# Sensor_Multiplexation.net
KiCad netlist of a schematic drawn in Altium Designer
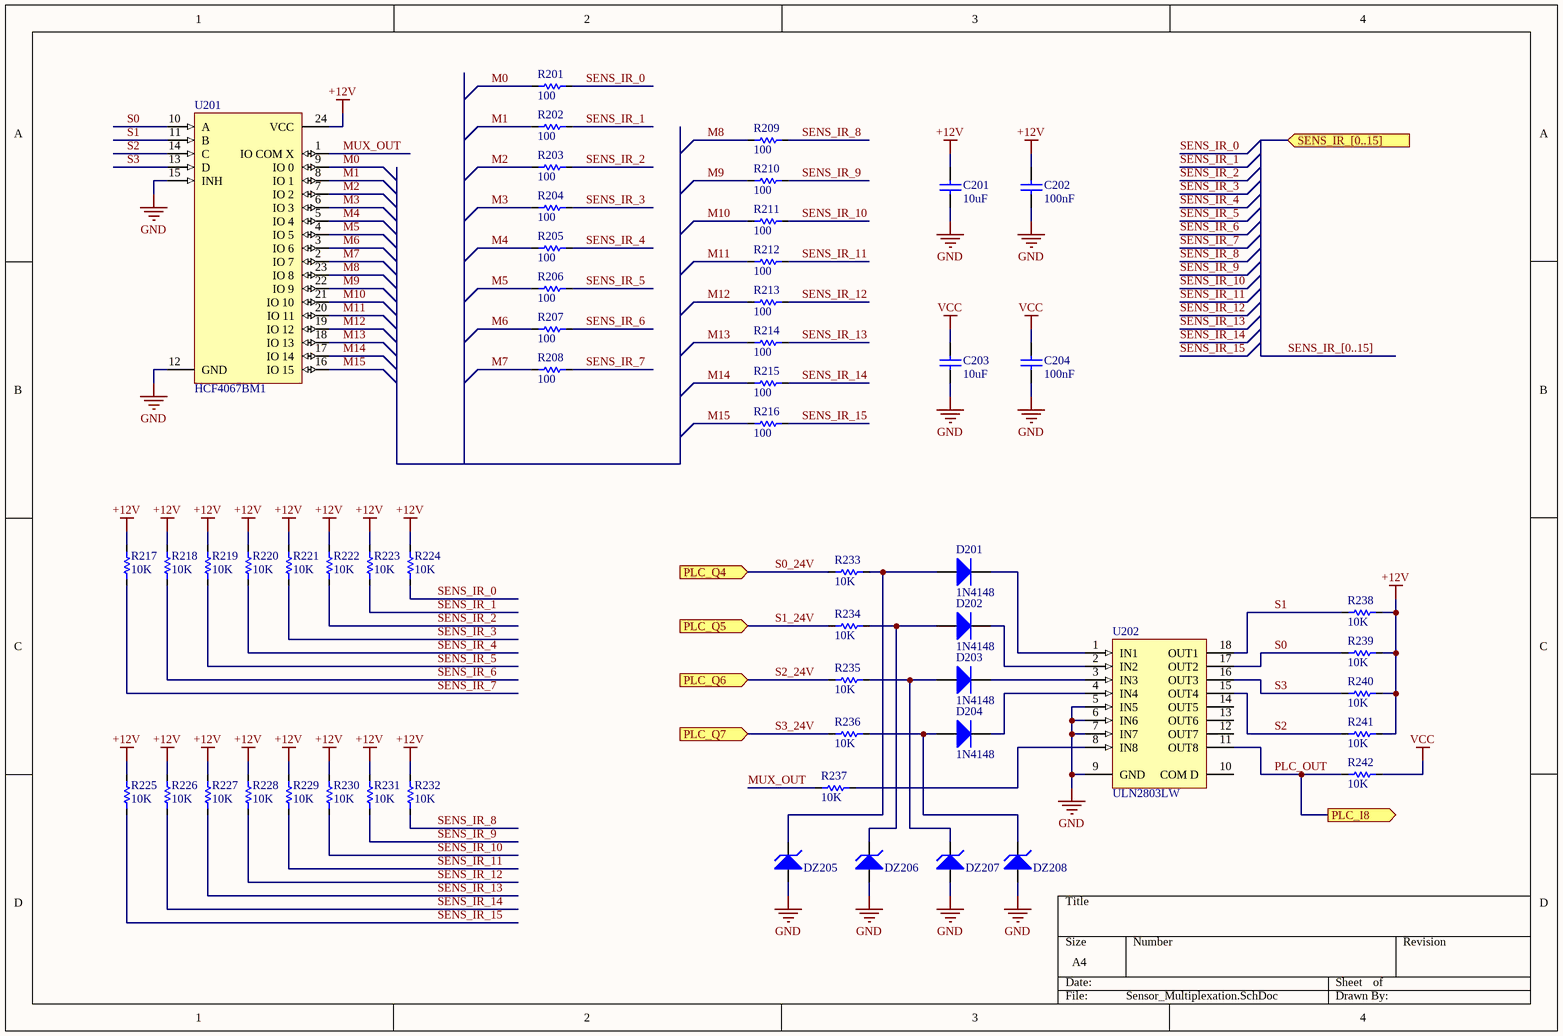
[diagram p0: Sensor_Multiplexation.SchDoc]

(export (version "E")
  (design (tool "Eeschema 10.0.6"))
  (components
    (comp (ref "C201")
      (value "Cap Ceramico SMD")
      (footprint "C0603")
      (description "Cap Ceramico SMD 0805")
      (fields (field (name "VALOR") "10uF"))
      (libsource (lib "RUF-Dispositivos-Grales") (part "Cap Ceramico SMD"))
    )
    (comp (ref "C202")
      (value "Cap Ceramico SMD")
      (footprint "C0603")
      (description "Cap Ceramico SMD 0805")
      (fields (field (name "VALOR") "100nF"))
      (libsource (lib "RUF-Dispositivos-Grales") (part "Cap Ceramico SMD"))
    )
    (comp (ref "C203")
      (value "Cap Ceramico SMD")
      (footprint "C0603")
      (description "Cap Ceramico SMD 0805")
      (fields (field (name "VALOR") "10uF"))
      (libsource (lib "RUF-Dispositivos-Grales") (part "Cap Ceramico SMD"))
    )
    (comp (ref "C204")
      (value "Cap Ceramico SMD")
      (footprint "C0603")
      (description "Cap Ceramico SMD 0805")
      (fields (field (name "VALOR") "100nF"))
      (libsource (lib "RUF-Dispositivos-Grales") (part "Cap Ceramico SMD"))
    )
    (comp (ref "D201")
      (value "Diodo Rectificador SMD")
      (footprint "SOD-80")
      (description "Diodo Rectificador")
      (fields (field (name "VALOR") "1N4148"))
      (libsource (lib "RUF-Dispositivos-Grales") (part "Diodo Rectificador SMD"))
    )
    (comp (ref "D202")
      (value "Diodo Rectificador SMD")
      (footprint "SOD-80")
      (description "Diodo Rectificador")
      (fields (field (name "VALOR") "1N4148"))
      (libsource (lib "RUF-Dispositivos-Grales") (part "Diodo Rectificador SMD"))
    )
    (comp (ref "D203")
      (value "Diodo Rectificador SMD")
      (footprint "SOD-80")
      (description "Diodo Rectificador")
      (fields (field (name "VALOR") "1N4148"))
      (libsource (lib "RUF-Dispositivos-Grales") (part "Diodo Rectificador SMD"))
    )
    (comp (ref "D204")
      (value "Diodo Rectificador SMD")
      (footprint "SOD-80")
      (description "Diodo Rectificador")
      (fields (field (name "VALOR") "1N4148"))
      (libsource (lib "RUF-Dispositivos-Grales") (part "Diodo Rectificador SMD"))
    )
    (comp (ref "DZ205")
      (value "Diodo Zenner SMD")
      (footprint "SOD-80")
      (description "Diodo zenner SMD")
      (libsource (lib "RUF-Dispositivos-Grales") (part "Diodo Zenner SMD"))
    )
    (comp (ref "DZ206")
      (value "Diodo Zenner SMD")
      (footprint "SOD-80")
      (description "Diodo zenner SMD")
      (libsource (lib "RUF-Dispositivos-Grales") (part "Diodo Zenner SMD"))
    )
    (comp (ref "DZ207")
      (value "Diodo Zenner SMD")
      (footprint "SOD-80")
      (description "Diodo zenner SMD")
      (libsource (lib "RUF-Dispositivos-Grales") (part "Diodo Zenner SMD"))
    )
    (comp (ref "DZ208")
      (value "Diodo Zenner SMD")
      (footprint "SOD-80")
      (description "Diodo zenner SMD")
      (libsource (lib "RUF-Dispositivos-Grales") (part "Diodo Zenner SMD"))
    )
    (comp (ref "R201")
      (value "Res SMD")
      (footprint "R0603")
      (description "Res Smd")
      (fields (field (name "VALOR") "100"))
      (libsource (lib "RUF-Dispositivos-Grales") (part "Res SMD"))
    )
    (comp (ref "R202")
      (value "Res SMD")
      (footprint "R0603")
      (description "Res Smd")
      (fields (field (name "VALOR") "100"))
      (libsource (lib "RUF-Dispositivos-Grales") (part "Res SMD"))
    )
    (comp (ref "R203")
      (value "Res SMD")
      (footprint "R0603")
      (description "Res Smd")
      (fields (field (name "VALOR") "100"))
      (libsource (lib "RUF-Dispositivos-Grales") (part "Res SMD"))
    )
    (comp (ref "R204")
      (value "Res SMD")
      (footprint "R0603")
      (description "Res Smd")
      (fields (field (name "VALOR") "100"))
      (libsource (lib "RUF-Dispositivos-Grales") (part "Res SMD"))
    )
    (comp (ref "R205")
      (value "Res SMD")
      (footprint "R0603")
      (description "Res Smd")
      (fields (field (name "VALOR") "100"))
      (libsource (lib "RUF-Dispositivos-Grales") (part "Res SMD"))
    )
    (comp (ref "R206")
      (value "Res SMD")
      (footprint "R0603")
      (description "Res Smd")
      (fields (field (name "VALOR") "100"))
      (libsource (lib "RUF-Dispositivos-Grales") (part "Res SMD"))
    )
    (comp (ref "R207")
      (value "Res SMD")
      (footprint "R0603")
      (description "Res Smd")
      (fields (field (name "VALOR") "100"))
      (libsource (lib "RUF-Dispositivos-Grales") (part "Res SMD"))
    )
    (comp (ref "R208")
      (value "Res SMD")
      (footprint "R0603")
      (description "Res Smd")
      (fields (field (name "VALOR") "100"))
      (libsource (lib "RUF-Dispositivos-Grales") (part "Res SMD"))
    )
    (comp (ref "R209")
      (value "Res SMD")
      (footprint "R0603")
      (description "Res Smd")
      (fields (field (name "VALOR") "100"))
      (libsource (lib "RUF-Dispositivos-Grales") (part "Res SMD"))
    )
    (comp (ref "R210")
      (value "Res SMD")
      (footprint "R0603")
      (description "Res Smd")
      (fields (field (name "VALOR") "100"))
      (libsource (lib "RUF-Dispositivos-Grales") (part "Res SMD"))
    )
    (comp (ref "R211")
      (value "Res SMD")
      (footprint "R0603")
      (description "Res Smd")
      (fields (field (name "VALOR") "100"))
      (libsource (lib "RUF-Dispositivos-Grales") (part "Res SMD"))
    )
    (comp (ref "R212")
      (value "Res SMD")
      (footprint "R0603")
      (description "Res Smd")
      (fields (field (name "VALOR") "100"))
      (libsource (lib "RUF-Dispositivos-Grales") (part "Res SMD"))
    )
    (comp (ref "R213")
      (value "Res SMD")
      (footprint "R0603")
      (description "Res Smd")
      (fields (field (name "VALOR") "100"))
      (libsource (lib "RUF-Dispositivos-Grales") (part "Res SMD"))
    )
    (comp (ref "R214")
      (value "Res SMD")
      (footprint "R0603")
      (description "Res Smd")
      (fields (field (name "VALOR") "100"))
      (libsource (lib "RUF-Dispositivos-Grales") (part "Res SMD"))
    )
    (comp (ref "R215")
      (value "Res SMD")
      (footprint "R0603")
      (description "Res Smd")
      (fields (field (name "VALOR") "100"))
      (libsource (lib "RUF-Dispositivos-Grales") (part "Res SMD"))
    )
    (comp (ref "R216")
      (value "Res SMD")
      (footprint "R0603")
      (description "Res Smd")
      (fields (field (name "VALOR") "100"))
      (libsource (lib "RUF-Dispositivos-Grales") (part "Res SMD"))
    )
    (comp (ref "R217")
      (value "Res SMD")
      (footprint "R0603")
      (description "Res Smd")
      (fields (field (name "VALOR") "10K"))
      (libsource (lib "RUF-Dispositivos-Grales") (part "Res SMD"))
    )
    (comp (ref "R218")
      (value "Res SMD")
      (footprint "R0603")
      (description "Res Smd")
      (fields (field (name "VALOR") "10K"))
      (libsource (lib "RUF-Dispositivos-Grales") (part "Res SMD"))
    )
    (comp (ref "R219")
      (value "Res SMD")
      (footprint "R0603")
      (description "Res Smd")
      (fields (field (name "VALOR") "10K"))
      (libsource (lib "RUF-Dispositivos-Grales") (part "Res SMD"))
    )
    (comp (ref "R220")
      (value "Res SMD")
      (footprint "R0603")
      (description "Res Smd")
      (fields (field (name "VALOR") "10K"))
      (libsource (lib "RUF-Dispositivos-Grales") (part "Res SMD"))
    )
    (comp (ref "R221")
      (value "Res SMD")
      (footprint "R0603")
      (description "Res Smd")
      (fields (field (name "VALOR") "10K"))
      (libsource (lib "RUF-Dispositivos-Grales") (part "Res SMD"))
    )
    (comp (ref "R222")
      (value "Res SMD")
      (footprint "R0603")
      (description "Res Smd")
      (fields (field (name "VALOR") "10K"))
      (libsource (lib "RUF-Dispositivos-Grales") (part "Res SMD"))
    )
    (comp (ref "R223")
      (value "Res SMD")
      (footprint "R0603")
      (description "Res Smd")
      (fields (field (name "VALOR") "10K"))
      (libsource (lib "RUF-Dispositivos-Grales") (part "Res SMD"))
    )
    (comp (ref "R224")
      (value "Res SMD")
      (footprint "R0603")
      (description "Res Smd")
      (fields (field (name "VALOR") "10K"))
      (libsource (lib "RUF-Dispositivos-Grales") (part "Res SMD"))
    )
    (comp (ref "R225")
      (value "Res SMD")
      (footprint "R0603")
      (description "Res Smd")
      (fields (field (name "VALOR") "10K"))
      (libsource (lib "RUF-Dispositivos-Grales") (part "Res SMD"))
    )
    (comp (ref "R226")
      (value "Res SMD")
      (footprint "R0603")
      (description "Res Smd")
      (fields (field (name "VALOR") "10K"))
      (libsource (lib "RUF-Dispositivos-Grales") (part "Res SMD"))
    )
    (comp (ref "R227")
      (value "Res SMD")
      (footprint "R0603")
      (description "Res Smd")
      (fields (field (name "VALOR") "10K"))
      (libsource (lib "RUF-Dispositivos-Grales") (part "Res SMD"))
    )
    (comp (ref "R228")
      (value "Res SMD")
      (footprint "R0603")
      (description "Res Smd")
      (fields (field (name "VALOR") "10K"))
      (libsource (lib "RUF-Dispositivos-Grales") (part "Res SMD"))
    )
    (comp (ref "R229")
      (value "Res SMD")
      (footprint "R0603")
      (description "Res Smd")
      (fields (field (name "VALOR") "10K"))
      (libsource (lib "RUF-Dispositivos-Grales") (part "Res SMD"))
    )
    (comp (ref "R230")
      (value "Res SMD")
      (footprint "R0603")
      (description "Res Smd")
      (fields (field (name "VALOR") "10K"))
      (libsource (lib "RUF-Dispositivos-Grales") (part "Res SMD"))
    )
    (comp (ref "R231")
      (value "Res SMD")
      (footprint "R0603")
      (description "Res Smd")
      (fields (field (name "VALOR") "10K"))
      (libsource (lib "RUF-Dispositivos-Grales") (part "Res SMD"))
    )
    (comp (ref "R232")
      (value "Res SMD")
      (footprint "R0603")
      (description "Res Smd")
      (fields (field (name "VALOR") "10K"))
      (libsource (lib "RUF-Dispositivos-Grales") (part "Res SMD"))
    )
    (comp (ref "R233")
      (value "Res SMD")
      (footprint "R0603")
      (description "Res Smd")
      (fields (field (name "VALOR") "10K"))
      (libsource (lib "RUF-Dispositivos-Grales") (part "Res SMD"))
    )
    (comp (ref "R234")
      (value "Res SMD")
      (footprint "R0603")
      (description "Res Smd")
      (fields (field (name "VALOR") "10K"))
      (libsource (lib "RUF-Dispositivos-Grales") (part "Res SMD"))
    )
    (comp (ref "R235")
      (value "Res SMD")
      (footprint "R0603")
      (description "Res Smd")
      (fields (field (name "VALOR") "10K"))
      (libsource (lib "RUF-Dispositivos-Grales") (part "Res SMD"))
    )
    (comp (ref "R236")
      (value "Res SMD")
      (footprint "R0603")
      (description "Res Smd")
      (fields (field (name "VALOR") "10K"))
      (libsource (lib "RUF-Dispositivos-Grales") (part "Res SMD"))
    )
    (comp (ref "R237")
      (value "Res SMD")
      (footprint "R0603")
      (description "Res Smd")
      (fields (field (name "VALOR") "10K"))
      (libsource (lib "RUF-Dispositivos-Grales") (part "Res SMD"))
    )
    (comp (ref "R238")
      (value "Res SMD")
      (footprint "R0603")
      (description "Res Smd")
      (fields (field (name "VALOR") "10K"))
      (libsource (lib "RUF-Dispositivos-Grales") (part "Res SMD"))
    )
    (comp (ref "R239")
      (value "Res SMD")
      (footprint "R0603")
      (description "Res Smd")
      (fields (field (name "VALOR") "10K"))
      (libsource (lib "RUF-Dispositivos-Grales") (part "Res SMD"))
    )
    (comp (ref "R240")
      (value "Res SMD")
      (footprint "R0603")
      (description "Res Smd")
      (fields (field (name "VALOR") "10K"))
      (libsource (lib "RUF-Dispositivos-Grales") (part "Res SMD"))
    )
    (comp (ref "R241")
      (value "Res SMD")
      (footprint "R0603")
      (description "Res Smd")
      (fields (field (name "VALOR") "10K"))
      (libsource (lib "RUF-Dispositivos-Grales") (part "Res SMD"))
    )
    (comp (ref "R242")
      (value "Res SMD")
      (footprint "R0603")
      (description "Res Smd")
      (fields (field (name "VALOR") "10K"))
      (libsource (lib "RUF-Dispositivos-Grales") (part "Res SMD"))
    )
    (comp (ref "U201")
      (value "HCF4067BM1")
      (footprint "SO24_M")
      (description "Analog Multiplexer/Demultiplexer")
      (fields (field (name "PUBLISHER") "Altium Limited"))
      (libsource (lib "ST Logic Multiplexer") (part "HCF4067BM1"))
    )
    (comp (ref "U202")
      (value "ULN2803LW")
      (footprint "LW18_M")
      (description "High-Voltage, High-Current Darlington Array")
      (fields (field (name "PUBLISHER") "Altium Limited"))
      (libsource (lib "Allegro Interface Darlington Driver") (part "ULN2803LW"))
    )
  )
  (nets
    (net (code "1") (name "+12V") (class "Default")
      (node (ref "C201") (pin "1") (pinfunction "1_1") (pintype "passive"))
      (node (ref "C202") (pin "1") (pinfunction "1_1") (pintype "passive"))
      (node (ref "R217") (pin "1") (pinfunction "1_1") (pintype "passive"))
      (node (ref "R218") (pin "1") (pinfunction "1_1") (pintype "passive"))
      (node (ref "R219") (pin "1") (pinfunction "1_1") (pintype "passive"))
      (node (ref "R220") (pin "1") (pinfunction "1_1") (pintype "passive"))
      (node (ref "R221") (pin "1") (pinfunction "1_1") (pintype "passive"))
      (node (ref "R222") (pin "1") (pinfunction "1_1") (pintype "passive"))
      (node (ref "R223") (pin "1") (pinfunction "1_1") (pintype "passive"))
      (node (ref "R224") (pin "1") (pinfunction "1_1") (pintype "passive"))
      (node (ref "R225") (pin "1") (pinfunction "1_1") (pintype "passive"))
      (node (ref "R226") (pin "1") (pinfunction "1_1") (pintype "passive"))
      (node (ref "R227") (pin "1") (pinfunction "1_1") (pintype "passive"))
      (node (ref "R228") (pin "1") (pinfunction "1_1") (pintype "passive"))
      (node (ref "R229") (pin "1") (pinfunction "1_1") (pintype "passive"))
      (node (ref "R230") (pin "1") (pinfunction "1_1") (pintype "passive"))
      (node (ref "R231") (pin "1") (pinfunction "1_1") (pintype "passive"))
      (node (ref "R232") (pin "1") (pinfunction "1_1") (pintype "passive"))
      (node (ref "R238") (pin "2") (pinfunction "2_2") (pintype "passive"))
      (node (ref "R239") (pin "2") (pinfunction "2_2") (pintype "passive"))
      (node (ref "R240") (pin "2") (pinfunction "2_2") (pintype "passive"))
      (node (ref "R241") (pin "2") (pinfunction "2_2") (pintype "passive"))
      (node (ref "U201") (pin "24") (pinfunction "VCC_24") (pintype "power_in"))
    )
    (net (code "2") (name "/M0") (class "Default")
      (node (ref "R201") (pin "2") (pinfunction "2_2") (pintype "passive"))
      (node (ref "U201") (pin "9") (pinfunction "IO_0_9") (pintype "bidirectional"))
    )
    (net (code "3") (name "/M1") (class "Default")
      (node (ref "R202") (pin "2") (pinfunction "2_2") (pintype "passive"))
      (node (ref "U201") (pin "8") (pinfunction "IO_1_8") (pintype "bidirectional"))
    )
    (net (code "4") (name "/M2") (class "Default")
      (node (ref "R203") (pin "2") (pinfunction "2_2") (pintype "passive"))
      (node (ref "U201") (pin "7") (pinfunction "IO_2_7") (pintype "bidirectional"))
    )
    (net (code "5") (name "/M3") (class "Default")
      (node (ref "R204") (pin "2") (pinfunction "2_2") (pintype "passive"))
      (node (ref "U201") (pin "6") (pinfunction "IO_3_6") (pintype "bidirectional"))
    )
    (net (code "6") (name "/M4") (class "Default")
      (node (ref "R205") (pin "2") (pinfunction "2_2") (pintype "passive"))
      (node (ref "U201") (pin "5") (pinfunction "IO_4_5") (pintype "bidirectional"))
    )
    (net (code "7") (name "/M5") (class "Default")
      (node (ref "R206") (pin "2") (pinfunction "2_2") (pintype "passive"))
      (node (ref "U201") (pin "4") (pinfunction "IO_5_4") (pintype "bidirectional"))
    )
    (net (code "8") (name "/M6") (class "Default")
      (node (ref "R207") (pin "2") (pinfunction "2_2") (pintype "passive"))
      (node (ref "U201") (pin "3") (pinfunction "IO_6_3") (pintype "bidirectional"))
    )
    (net (code "9") (name "/M7") (class "Default")
      (node (ref "R208") (pin "2") (pinfunction "2_2") (pintype "passive"))
      (node (ref "U201") (pin "2") (pinfunction "IO_7_2") (pintype "bidirectional"))
    )
    (net (code "10") (name "/M8") (class "Default")
      (node (ref "R209") (pin "2") (pinfunction "2_2") (pintype "passive"))
      (node (ref "U201") (pin "23") (pinfunction "IO_8_23") (pintype "bidirectional"))
    )
    (net (code "11") (name "/M9") (class "Default")
      (node (ref "R210") (pin "2") (pinfunction "2_2") (pintype "passive"))
      (node (ref "U201") (pin "22") (pinfunction "IO_9_22") (pintype "bidirectional"))
    )
    (net (code "12") (name "/M10") (class "Default")
      (node (ref "R211") (pin "2") (pinfunction "2_2") (pintype "passive"))
      (node (ref "U201") (pin "21") (pinfunction "IO_10_21") (pintype "bidirectional"))
    )
    (net (code "13") (name "/M11") (class "Default")
      (node (ref "R212") (pin "2") (pinfunction "2_2") (pintype "passive"))
      (node (ref "U201") (pin "20") (pinfunction "IO_11_20") (pintype "bidirectional"))
    )
    (net (code "14") (name "/M12") (class "Default")
      (node (ref "R213") (pin "2") (pinfunction "2_2") (pintype "passive"))
      (node (ref "U201") (pin "19") (pinfunction "IO_12_19") (pintype "bidirectional"))
    )
    (net (code "15") (name "/M13") (class "Default")
      (node (ref "R214") (pin "2") (pinfunction "2_2") (pintype "passive"))
      (node (ref "U201") (pin "18") (pinfunction "IO_13_18") (pintype "bidirectional"))
    )
    (net (code "16") (name "/M14") (class "Default")
      (node (ref "R215") (pin "2") (pinfunction "2_2") (pintype "passive"))
      (node (ref "U201") (pin "17") (pinfunction "IO_14_17") (pintype "bidirectional"))
    )
    (net (code "17") (name "/M15") (class "Default")
      (node (ref "R216") (pin "2") (pinfunction "2_2") (pintype "passive"))
      (node (ref "U201") (pin "16") (pinfunction "IO_15_16") (pintype "bidirectional"))
    )
    (net (code "18") (name "/MUX_OUT") (class "Default")
      (node (ref "R237") (pin "1") (pinfunction "1_1") (pintype "passive"))
      (node (ref "U201") (pin "1") (pinfunction "IO_COM_X_1") (pintype "bidirectional"))
    )
    (net (code "19") (name "/PLC_OUT") (class "Default")
      (node (ref "R242") (pin "1") (pinfunction "1_1") (pintype "passive"))
      (node (ref "U202") (pin "11") (pinfunction "OUT8_11") (pintype "open_collector"))
    )
    (net (code "20") (name "/S0") (class "Default")
      (node (ref "R239") (pin "1") (pinfunction "1_1") (pintype "passive"))
      (node (ref "U201") (pin "10") (pinfunction "A_10") (pintype "input"))
      (node (ref "U202") (pin "17") (pinfunction "OUT2_17") (pintype "open_collector"))
    )
    (net (code "21") (name "/S0_24V") (class "Default")
      (node (ref "R233") (pin "1") (pinfunction "1_1") (pintype "passive"))
    )
    (net (code "22") (name "/S1") (class "Default")
      (node (ref "R238") (pin "1") (pinfunction "1_1") (pintype "passive"))
      (node (ref "U201") (pin "11") (pinfunction "B_11") (pintype "input"))
      (node (ref "U202") (pin "18") (pinfunction "OUT1_18") (pintype "open_collector"))
    )
    (net (code "23") (name "/S1_24V") (class "Default")
      (node (ref "R234") (pin "1") (pinfunction "1_1") (pintype "passive"))
    )
    (net (code "24") (name "/S2") (class "Default")
      (node (ref "R241") (pin "1") (pinfunction "1_1") (pintype "passive"))
      (node (ref "U201") (pin "14") (pinfunction "C_14") (pintype "input"))
      (node (ref "U202") (pin "15") (pinfunction "OUT4_15") (pintype "open_collector"))
    )
    (net (code "25") (name "/S2_24V") (class "Default")
      (node (ref "R235") (pin "1") (pinfunction "1_1") (pintype "passive"))
    )
    (net (code "26") (name "/S3") (class "Default")
      (node (ref "R240") (pin "1") (pinfunction "1_1") (pintype "passive"))
      (node (ref "U201") (pin "13") (pinfunction "D_13") (pintype "input"))
      (node (ref "U202") (pin "16") (pinfunction "OUT3_16") (pintype "open_collector"))
    )
    (net (code "27") (name "/S3_24V") (class "Default")
      (node (ref "R236") (pin "1") (pinfunction "1_1") (pintype "passive"))
    )
    (net (code "28") (name "/SENS_IR_0") (class "Default")
      (node (ref "R201") (pin "1") (pinfunction "1_1") (pintype "passive"))
      (node (ref "R224") (pin "2") (pinfunction "2_2") (pintype "passive"))
    )
    (net (code "29") (name "/SENS_IR_1") (class "Default")
      (node (ref "R202") (pin "1") (pinfunction "1_1") (pintype "passive"))
      (node (ref "R223") (pin "2") (pinfunction "2_2") (pintype "passive"))
    )
    (net (code "30") (name "/SENS_IR_2") (class "Default")
      (node (ref "R203") (pin "1") (pinfunction "1_1") (pintype "passive"))
      (node (ref "R222") (pin "2") (pinfunction "2_2") (pintype "passive"))
    )
    (net (code "31") (name "/SENS_IR_3") (class "Default")
      (node (ref "R204") (pin "1") (pinfunction "1_1") (pintype "passive"))
      (node (ref "R221") (pin "2") (pinfunction "2_2") (pintype "passive"))
    )
    (net (code "32") (name "/SENS_IR_4") (class "Default")
      (node (ref "R205") (pin "1") (pinfunction "1_1") (pintype "passive"))
      (node (ref "R220") (pin "2") (pinfunction "2_2") (pintype "passive"))
    )
    (net (code "33") (name "/SENS_IR_5") (class "Default")
      (node (ref "R206") (pin "1") (pinfunction "1_1") (pintype "passive"))
      (node (ref "R219") (pin "2") (pinfunction "2_2") (pintype "passive"))
    )
    (net (code "34") (name "/SENS_IR_6") (class "Default")
      (node (ref "R207") (pin "1") (pinfunction "1_1") (pintype "passive"))
      (node (ref "R218") (pin "2") (pinfunction "2_2") (pintype "passive"))
    )
    (net (code "35") (name "/SENS_IR_7") (class "Default")
      (node (ref "R208") (pin "1") (pinfunction "1_1") (pintype "passive"))
      (node (ref "R217") (pin "2") (pinfunction "2_2") (pintype "passive"))
    )
    (net (code "36") (name "/SENS_IR_8") (class "Default")
      (node (ref "R209") (pin "1") (pinfunction "1_1") (pintype "passive"))
      (node (ref "R232") (pin "2") (pinfunction "2_2") (pintype "passive"))
    )
    (net (code "37") (name "/SENS_IR_9") (class "Default")
      (node (ref "R210") (pin "1") (pinfunction "1_1") (pintype "passive"))
      (node (ref "R231") (pin "2") (pinfunction "2_2") (pintype "passive"))
    )
    (net (code "38") (name "/SENS_IR_10") (class "Default")
      (node (ref "R211") (pin "1") (pinfunction "1_1") (pintype "passive"))
      (node (ref "R230") (pin "2") (pinfunction "2_2") (pintype "passive"))
    )
    (net (code "39") (name "/SENS_IR_11") (class "Default")
      (node (ref "R212") (pin "1") (pinfunction "1_1") (pintype "passive"))
      (node (ref "R229") (pin "2") (pinfunction "2_2") (pintype "passive"))
    )
    (net (code "40") (name "/SENS_IR_12") (class "Default")
      (node (ref "R213") (pin "1") (pinfunction "1_1") (pintype "passive"))
      (node (ref "R228") (pin "2") (pinfunction "2_2") (pintype "passive"))
    )
    (net (code "41") (name "/SENS_IR_13") (class "Default")
      (node (ref "R214") (pin "1") (pinfunction "1_1") (pintype "passive"))
      (node (ref "R227") (pin "2") (pinfunction "2_2") (pintype "passive"))
    )
    (net (code "42") (name "/SENS_IR_14") (class "Default")
      (node (ref "R215") (pin "1") (pinfunction "1_1") (pintype "passive"))
      (node (ref "R226") (pin "2") (pinfunction "2_2") (pintype "passive"))
    )
    (net (code "43") (name "/SENS_IR_15") (class "Default")
      (node (ref "R216") (pin "1") (pinfunction "1_1") (pintype "passive"))
      (node (ref "R225") (pin "2") (pinfunction "2_2") (pintype "passive"))
    )
    (net (code "45") (name "GND") (class "Default")
      (node (ref "C201") (pin "2") (pinfunction "2_2") (pintype "passive"))
      (node (ref "C202") (pin "2") (pinfunction "2_2") (pintype "passive"))
      (node (ref "C203") (pin "2") (pinfunction "2_2") (pintype "passive"))
      (node (ref "C204") (pin "2") (pinfunction "2_2") (pintype "passive"))
      (node (ref "DZ205") (pin "1") (pinfunction "A_1") (pintype "passive"))
      (node (ref "DZ206") (pin "1") (pinfunction "A_1") (pintype "passive"))
      (node (ref "DZ207") (pin "1") (pinfunction "A_1") (pintype "passive"))
      (node (ref "DZ208") (pin "1") (pinfunction "A_1") (pintype "passive"))
      (node (ref "U201") (pin "12") (pinfunction "GND_12") (pintype "power_in"))
      (node (ref "U201") (pin "15") (pinfunction "INH_15") (pintype "input"))
      (node (ref "U202") (pin "5") (pinfunction "IN5_5") (pintype "input"))
      (node (ref "U202") (pin "6") (pinfunction "IN6_6") (pintype "input"))
      (node (ref "U202") (pin "7") (pinfunction "IN7_7") (pintype "input"))
      (node (ref "U202") (pin "9") (pinfunction "GND_9") (pintype "power_in"))
    )
    (net (code "46") (name "Net-(D201-A)") (class "Default")
      (node (ref "D201") (pin "1") (pinfunction "A_1") (pintype "passive"))
      (node (ref "DZ205") (pin "2") (pinfunction "K_2") (pintype "passive"))
      (node (ref "R233") (pin "2") (pinfunction "2_2") (pintype "passive"))
    )
    (net (code "47") (name "Net-(D201-K)") (class "Default")
      (node (ref "D201") (pin "2") (pinfunction "K_2") (pintype "passive"))
      (node (ref "U202") (pin "1") (pinfunction "IN1_1") (pintype "input"))
    )
    (net (code "48") (name "Net-(D202-A)") (class "Default")
      (node (ref "D202") (pin "1") (pinfunction "A_1") (pintype "passive"))
      (node (ref "DZ206") (pin "2") (pinfunction "K_2") (pintype "passive"))
      (node (ref "R234") (pin "2") (pinfunction "2_2") (pintype "passive"))
    )
    (net (code "49") (name "Net-(D202-K)") (class "Default")
      (node (ref "D202") (pin "2") (pinfunction "K_2") (pintype "passive"))
      (node (ref "U202") (pin "2") (pinfunction "IN2_2") (pintype "input"))
    )
    (net (code "50") (name "Net-(D203-A)") (class "Default")
      (node (ref "D203") (pin "1") (pinfunction "A_1") (pintype "passive"))
      (node (ref "DZ207") (pin "2") (pinfunction "K_2") (pintype "passive"))
      (node (ref "R235") (pin "2") (pinfunction "2_2") (pintype "passive"))
    )
    (net (code "51") (name "Net-(D203-K)") (class "Default")
      (node (ref "D203") (pin "2") (pinfunction "K_2") (pintype "passive"))
      (node (ref "U202") (pin "3") (pinfunction "IN3_3") (pintype "input"))
    )
    (net (code "52") (name "Net-(D204-A)") (class "Default")
      (node (ref "D204") (pin "1") (pinfunction "A_1") (pintype "passive"))
      (node (ref "DZ208") (pin "2") (pinfunction "K_2") (pintype "passive"))
      (node (ref "R236") (pin "2") (pinfunction "2_2") (pintype "passive"))
    )
    (net (code "53") (name "Net-(D204-K)") (class "Default")
      (node (ref "D204") (pin "2") (pinfunction "K_2") (pintype "passive"))
      (node (ref "U202") (pin "4") (pinfunction "IN4_4") (pintype "input"))
    )
    (net (code "54") (name "Net-(U202-IN8)") (class "Default")
      (node (ref "R237") (pin "2") (pinfunction "2_2") (pintype "passive"))
      (node (ref "U202") (pin "8") (pinfunction "IN8_8") (pintype "input"))
    )
    (net (code "55") (name "VCC") (class "Default")
      (node (ref "C203") (pin "1") (pinfunction "1_1") (pintype "passive"))
      (node (ref "C204") (pin "1") (pinfunction "1_1") (pintype "passive"))
      (node (ref "R242") (pin "2") (pinfunction "2_2") (pintype "passive"))
    )
    (net (code "56") (name "unconnected-(U202-COM_D-Pad10)") (class "Default")
      (node (ref "U202") (pin "10") (pinfunction "COM_D_10") (pintype "passive"))
    )
    (net (code "57") (name "unconnected-(U202-OUT5-Pad14)") (class "Default")
      (node (ref "U202") (pin "14") (pinfunction "OUT5_14") (pintype "open_collector"))
    )
    (net (code "58") (name "unconnected-(U202-OUT6-Pad13)") (class "Default")
      (node (ref "U202") (pin "13") (pinfunction "OUT6_13") (pintype "open_collector"))
    )
    (net (code "59") (name "unconnected-(U202-OUT7-Pad12)") (class "Default")
      (node (ref "U202") (pin "12") (pinfunction "OUT7_12") (pintype "open_collector"))
    )
  )
)
